# 05-Signal_Conditioning.net
KiCad netlist of a schematic drawn in Altium Designer
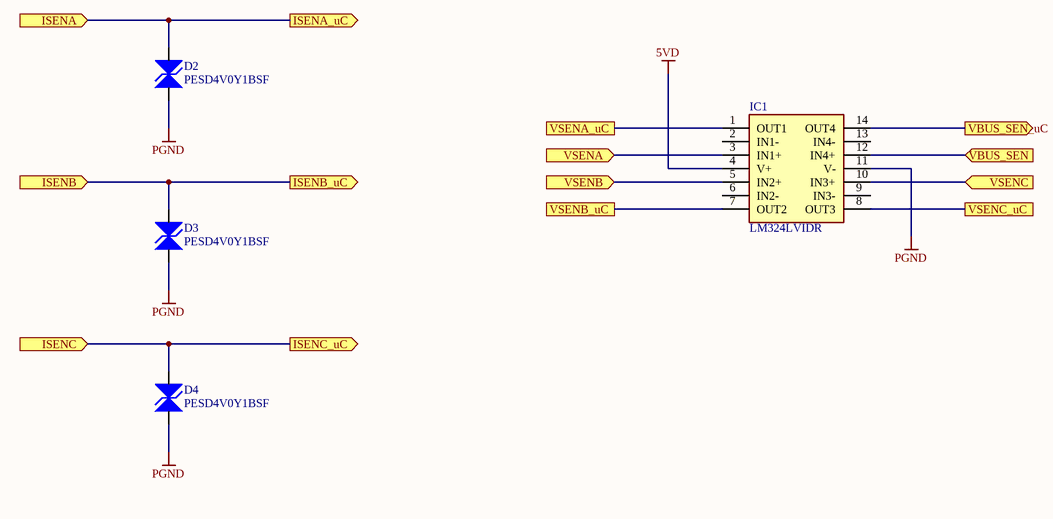
[diagram p0: 05-Signal_Conditioning.SchDoc]

(export (version "E")
  (design (tool "Eeschema 10.0.6"))
  (components
    (comp (ref "D2")
      (value "PESD4V0Y1BSF")
      (footprint "DFN40P60X32-2M")
      (libsource (lib "driver_board_lib") (part "PESD4V0Y1BSF"))
    )
    (comp (ref "D3")
      (value "PESD4V0Y1BSF")
      (footprint "DFN40P60X32-2M")
      (libsource (lib "driver_board_lib") (part "PESD4V0Y1BSF"))
    )
    (comp (ref "D4")
      (value "PESD4V0Y1BSF")
      (footprint "DFN40P60X32-2M")
      (libsource (lib "driver_board_lib") (part "PESD4V0Y1BSF"))
    )
    (comp (ref "IC1")
      (value "LM324LVIDR")
      (footprint "SamacSys:SOIC127P600X175-14N")
      (description "Integrated Circuit")
      (fields (field (name "MOUSER PART NUMBER") "595-LM324LVIDR"))
      (libsource (lib "*") (part "LM324LVIDR"))
    )
  )
  (nets
    (net (code "1") (name "/ISENA") (class "Default")
      (node (ref "D2") (pin "2") (pinfunction "2_2") (pintype "passive"))
    )
    (net (code "2") (name "/ISENB") (class "Default")
      (node (ref "D3") (pin "2") (pinfunction "2_2") (pintype "passive"))
    )
    (net (code "3") (name "/ISENC") (class "Default")
      (node (ref "D4") (pin "2") (pinfunction "2_2") (pintype "passive"))
    )
    (net (code "4") (name "/VBUS_SEN") (class "Default")
      (node (ref "IC1") (pin "12") (pinfunction "IN4+_12") (pintype "passive"))
    )
    (net (code "5") (name "/VBUS_SEN_uC") (class "Default")
      (node (ref "IC1") (pin "14") (pinfunction "OUT4_14") (pintype "passive"))
    )
    (net (code "6") (name "/VSENA") (class "Default")
      (node (ref "IC1") (pin "3") (pinfunction "IN1+_3") (pintype "passive"))
    )
    (net (code "7") (name "/VSENA_uC") (class "Default")
      (node (ref "IC1") (pin "1") (pinfunction "OUT1_1") (pintype "passive"))
    )
    (net (code "8") (name "/VSENB") (class "Default")
      (node (ref "IC1") (pin "5") (pinfunction "IN2+_5") (pintype "passive"))
    )
    (net (code "9") (name "/VSENB_uC") (class "Default")
      (node (ref "IC1") (pin "7") (pinfunction "OUT2_7") (pintype "passive"))
    )
    (net (code "10") (name "/VSENC") (class "Default")
      (node (ref "IC1") (pin "10") (pinfunction "IN3+_10") (pintype "passive"))
    )
    (net (code "11") (name "/VSENC_uC") (class "Default")
      (node (ref "IC1") (pin "8") (pinfunction "OUT3_8") (pintype "passive"))
    )
    (net (code "12") (name "5VD") (class "Default")
      (node (ref "IC1") (pin "4") (pinfunction "V+_4") (pintype "passive"))
    )
    (net (code "13") (name "PGND") (class "Default")
      (node (ref "D2") (pin "1") (pinfunction "1_1") (pintype "passive"))
      (node (ref "D3") (pin "1") (pinfunction "1_1") (pintype "passive"))
      (node (ref "D4") (pin "1") (pinfunction "1_1") (pintype "passive"))
      (node (ref "IC1") (pin "11") (pinfunction "V-_11") (pintype "passive"))
    )
    (net (code "14") (name "unconnected-(IC1-IN1--Pad2)") (class "Default")
      (node (ref "IC1") (pin "2") (pinfunction "IN1-_2") (pintype "passive"))
    )
    (net (code "15") (name "unconnected-(IC1-IN2--Pad6)") (class "Default")
      (node (ref "IC1") (pin "6") (pinfunction "IN2-_6") (pintype "passive"))
    )
    (net (code "16") (name "unconnected-(IC1-IN3--Pad9)") (class "Default")
      (node (ref "IC1") (pin "9") (pinfunction "IN3-_9") (pintype "passive"))
    )
    (net (code "17") (name "unconnected-(IC1-IN4--Pad13)") (class "Default")
      (node (ref "IC1") (pin "13") (pinfunction "IN4-_13") (pintype "passive"))
    )
  )
)
